# NanoBud.net
KiCad netlist of a schematic drawn in EAGLE
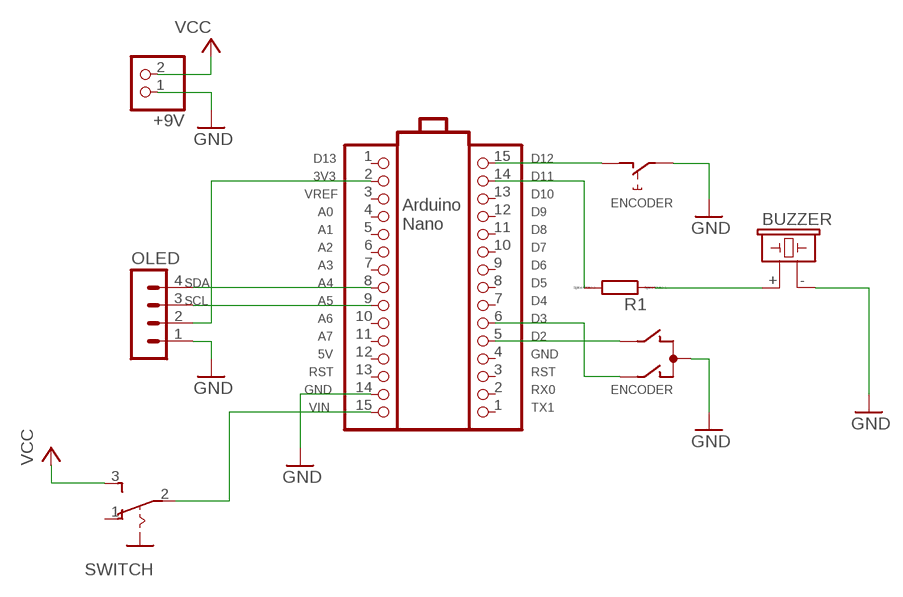
[diagram p0: schematic, sheet 1]

(export (version "E")
  (design (tool "Eeschema 10.0.6"))
  (components
    (comp (ref "+9V")
      (value "PINHD-1X2")
      (footprint "eagle-import:1X02")
      (libsource (lib "eagle-import") (part "PINHD-1X2"))
    )
    (comp (ref "BUZZER")
      (value "F/CM12P")
      (footprint "eagle-import:F_CM12P")
      (libsource (lib "eagle-import") (part "F/CM12P"))
    )
    (comp (ref "ENCODER")
      (value "EC12E_SW")
      (footprint "eagle-import:ALPS_EC12E_SW")
      (fields (field (name "MPN") "EC12E2424407"))
      (libsource (lib "eagle-import") (part "EC12E_SW"))
    )
    (comp (ref "OLED")
      (value "MA04-1")
      (footprint "eagle-import:MA04-1")
      (libsource (lib "eagle-import") (part "MA04-1"))
    )
    (comp (ref "R1")
      (value "R0204/7")
      (footprint "eagle-import:0204_7")
      (libsource (lib "eagle-import") (part "R0204/7"))
    )
    (comp (ref "SV1")
      (value "PINHD-1X15")
      (footprint "eagle-import:1X15")
      (libsource (lib "eagle-import") (part "PINHD-1X15"))
    )
    (comp (ref "SV2")
      (value "PINHD-1X15")
      (footprint "eagle-import:1X15")
      (libsource (lib "eagle-import") (part "PINHD-1X15"))
    )
    (comp (ref "SWITCH")
      (value "M251")
      (footprint "eagle-import:M251")
      (libsource (lib "eagle-import") (part "M251"))
    )
  )
  (nets
    (net (code "1") (name "GND") (class "Default")
      (node (ref "+9V") (pin "1") (pinfunction "1_1") (pintype "passive"))
      (node (ref "BUZZER") (pin "-") (pinfunction "2_-") (pintype "passive"))
      (node (ref "ENCODER") (pin "C") (pinfunction "C_C") (pintype "passive"))
      (node (ref "ENCODER") (pin "E") (pinfunction "2_E") (pintype "passive"))
      (node (ref "OLED") (pin "1") (pinfunction "1_1") (pintype "passive"))
      (node (ref "SV2") (pin "14") (pinfunction "14_14") (pintype "passive"))
    )
    (net (code "2") (name "Net-(BUZZER-1)") (class "Default")
      (node (ref "BUZZER") (pin "+") (pinfunction "1_+") (pintype "passive"))
      (node (ref "R1") (pin "1") (pinfunction "1_1") (pintype "passive"))
    )
    (net (code "3") (name "Net-(ENCODER-PadA)") (class "Default")
      (node (ref "ENCODER") (pin "A") (pinfunction "A_A") (pintype "passive"))
      (node (ref "SV1") (pin "6") (pinfunction "6_6") (pintype "passive"))
    )
    (net (code "4") (name "Net-(ENCODER-PadB)") (class "Default")
      (node (ref "ENCODER") (pin "B") (pinfunction "B_B") (pintype "passive"))
      (node (ref "SV1") (pin "5") (pinfunction "5_5") (pintype "passive"))
    )
    (net (code "5") (name "Net-(ENCODERB-1)") (class "Default")
      (node (ref "ENCODER") (pin "D") (pinfunction "1_D") (pintype "passive"))
      (node (ref "SV1") (pin "15") (pinfunction "15_15") (pintype "passive"))
    )
    (net (code "6") (name "Net-(OLED-Pad2)") (class "Default")
      (node (ref "OLED") (pin "2") (pinfunction "2_2") (pintype "passive"))
      (node (ref "SV2") (pin "2") (pinfunction "2_2") (pintype "passive"))
    )
    (net (code "7") (name "Net-(OLED-Pad3)") (class "Default")
      (node (ref "OLED") (pin "3") (pinfunction "3_3") (pintype "passive"))
      (node (ref "SV2") (pin "9") (pinfunction "9_9") (pintype "passive"))
    )
    (net (code "8") (name "Net-(OLED-Pad4)") (class "Default")
      (node (ref "OLED") (pin "4") (pinfunction "4_4") (pintype "passive"))
      (node (ref "SV2") (pin "8") (pinfunction "8_8") (pintype "passive"))
    )
    (net (code "9") (name "Net-(R1-Pad2)") (class "Default")
      (node (ref "R1") (pin "2") (pinfunction "2_2") (pintype "passive"))
      (node (ref "SV1") (pin "14") (pinfunction "14_14") (pintype "passive"))
    )
    (net (code "10") (name "Net-(SWITCH-P)") (class "Default")
      (node (ref "SV2") (pin "15") (pinfunction "15_15") (pintype "passive"))
      (node (ref "SWITCH") (pin "2") (pinfunction "P_2") (pintype "passive"))
    )
    (net (code "11") (name "VCC") (class "Default")
      (node (ref "+9V") (pin "2") (pinfunction "2_2") (pintype "passive"))
      (node (ref "SWITCH") (pin "3") (pinfunction "S_3") (pintype "passive"))
    )
    (net (code "12") (name "unconnected-(SV1-Pad1)") (class "Default")
      (node (ref "SV1") (pin "1") (pinfunction "1_1") (pintype "passive"))
    )
    (net (code "13") (name "unconnected-(SV1-Pad2)") (class "Default")
      (node (ref "SV1") (pin "2") (pinfunction "2_2") (pintype "passive"))
    )
    (net (code "14") (name "unconnected-(SV1-Pad3)") (class "Default")
      (node (ref "SV1") (pin "3") (pinfunction "3_3") (pintype "passive"))
    )
    (net (code "15") (name "unconnected-(SV1-Pad4)") (class "Default")
      (node (ref "SV1") (pin "4") (pinfunction "4_4") (pintype "passive"))
    )
    (net (code "16") (name "unconnected-(SV1-Pad7)") (class "Default")
      (node (ref "SV1") (pin "7") (pinfunction "7_7") (pintype "passive"))
    )
    (net (code "17") (name "unconnected-(SV1-Pad8)") (class "Default")
      (node (ref "SV1") (pin "8") (pinfunction "8_8") (pintype "passive"))
    )
    (net (code "18") (name "unconnected-(SV1-Pad9)") (class "Default")
      (node (ref "SV1") (pin "9") (pinfunction "9_9") (pintype "passive"))
    )
    (net (code "19") (name "unconnected-(SV1-Pad10)") (class "Default")
      (node (ref "SV1") (pin "10") (pinfunction "10_10") (pintype "passive"))
    )
    (net (code "20") (name "unconnected-(SV1-Pad11)") (class "Default")
      (node (ref "SV1") (pin "11") (pinfunction "11_11") (pintype "passive"))
    )
    (net (code "21") (name "unconnected-(SV1-Pad12)") (class "Default")
      (node (ref "SV1") (pin "12") (pinfunction "12_12") (pintype "passive"))
    )
    (net (code "22") (name "unconnected-(SV1-Pad13)") (class "Default")
      (node (ref "SV1") (pin "13") (pinfunction "13_13") (pintype "passive"))
    )
    (net (code "23") (name "unconnected-(SV2-Pad1)") (class "Default")
      (node (ref "SV2") (pin "1") (pinfunction "1_1") (pintype "passive"))
    )
    (net (code "24") (name "unconnected-(SV2-Pad3)") (class "Default")
      (node (ref "SV2") (pin "3") (pinfunction "3_3") (pintype "passive"))
    )
    (net (code "25") (name "unconnected-(SV2-Pad4)") (class "Default")
      (node (ref "SV2") (pin "4") (pinfunction "4_4") (pintype "passive"))
    )
    (net (code "26") (name "unconnected-(SV2-Pad5)") (class "Default")
      (node (ref "SV2") (pin "5") (pinfunction "5_5") (pintype "passive"))
    )
    (net (code "27") (name "unconnected-(SV2-Pad6)") (class "Default")
      (node (ref "SV2") (pin "6") (pinfunction "6_6") (pintype "passive"))
    )
    (net (code "28") (name "unconnected-(SV2-Pad7)") (class "Default")
      (node (ref "SV2") (pin "7") (pinfunction "7_7") (pintype "passive"))
    )
    (net (code "29") (name "unconnected-(SV2-Pad10)") (class "Default")
      (node (ref "SV2") (pin "10") (pinfunction "10_10") (pintype "passive"))
    )
    (net (code "30") (name "unconnected-(SV2-Pad11)") (class "Default")
      (node (ref "SV2") (pin "11") (pinfunction "11_11") (pintype "passive"))
    )
    (net (code "31") (name "unconnected-(SV2-Pad12)") (class "Default")
      (node (ref "SV2") (pin "12") (pinfunction "12_12") (pintype "passive"))
    )
    (net (code "32") (name "unconnected-(SV2-Pad13)") (class "Default")
      (node (ref "SV2") (pin "13") (pinfunction "13_13") (pintype "passive"))
    )
    (net (code "33") (name "unconnected-(SWITCH-O-Pad1)") (class "Default")
      (node (ref "SWITCH") (pin "1") (pinfunction "O_1") (pintype "passive"))
    )
  )
)
